# Temperature.net
KiCad netlist of a schematic drawn in Altium Designer
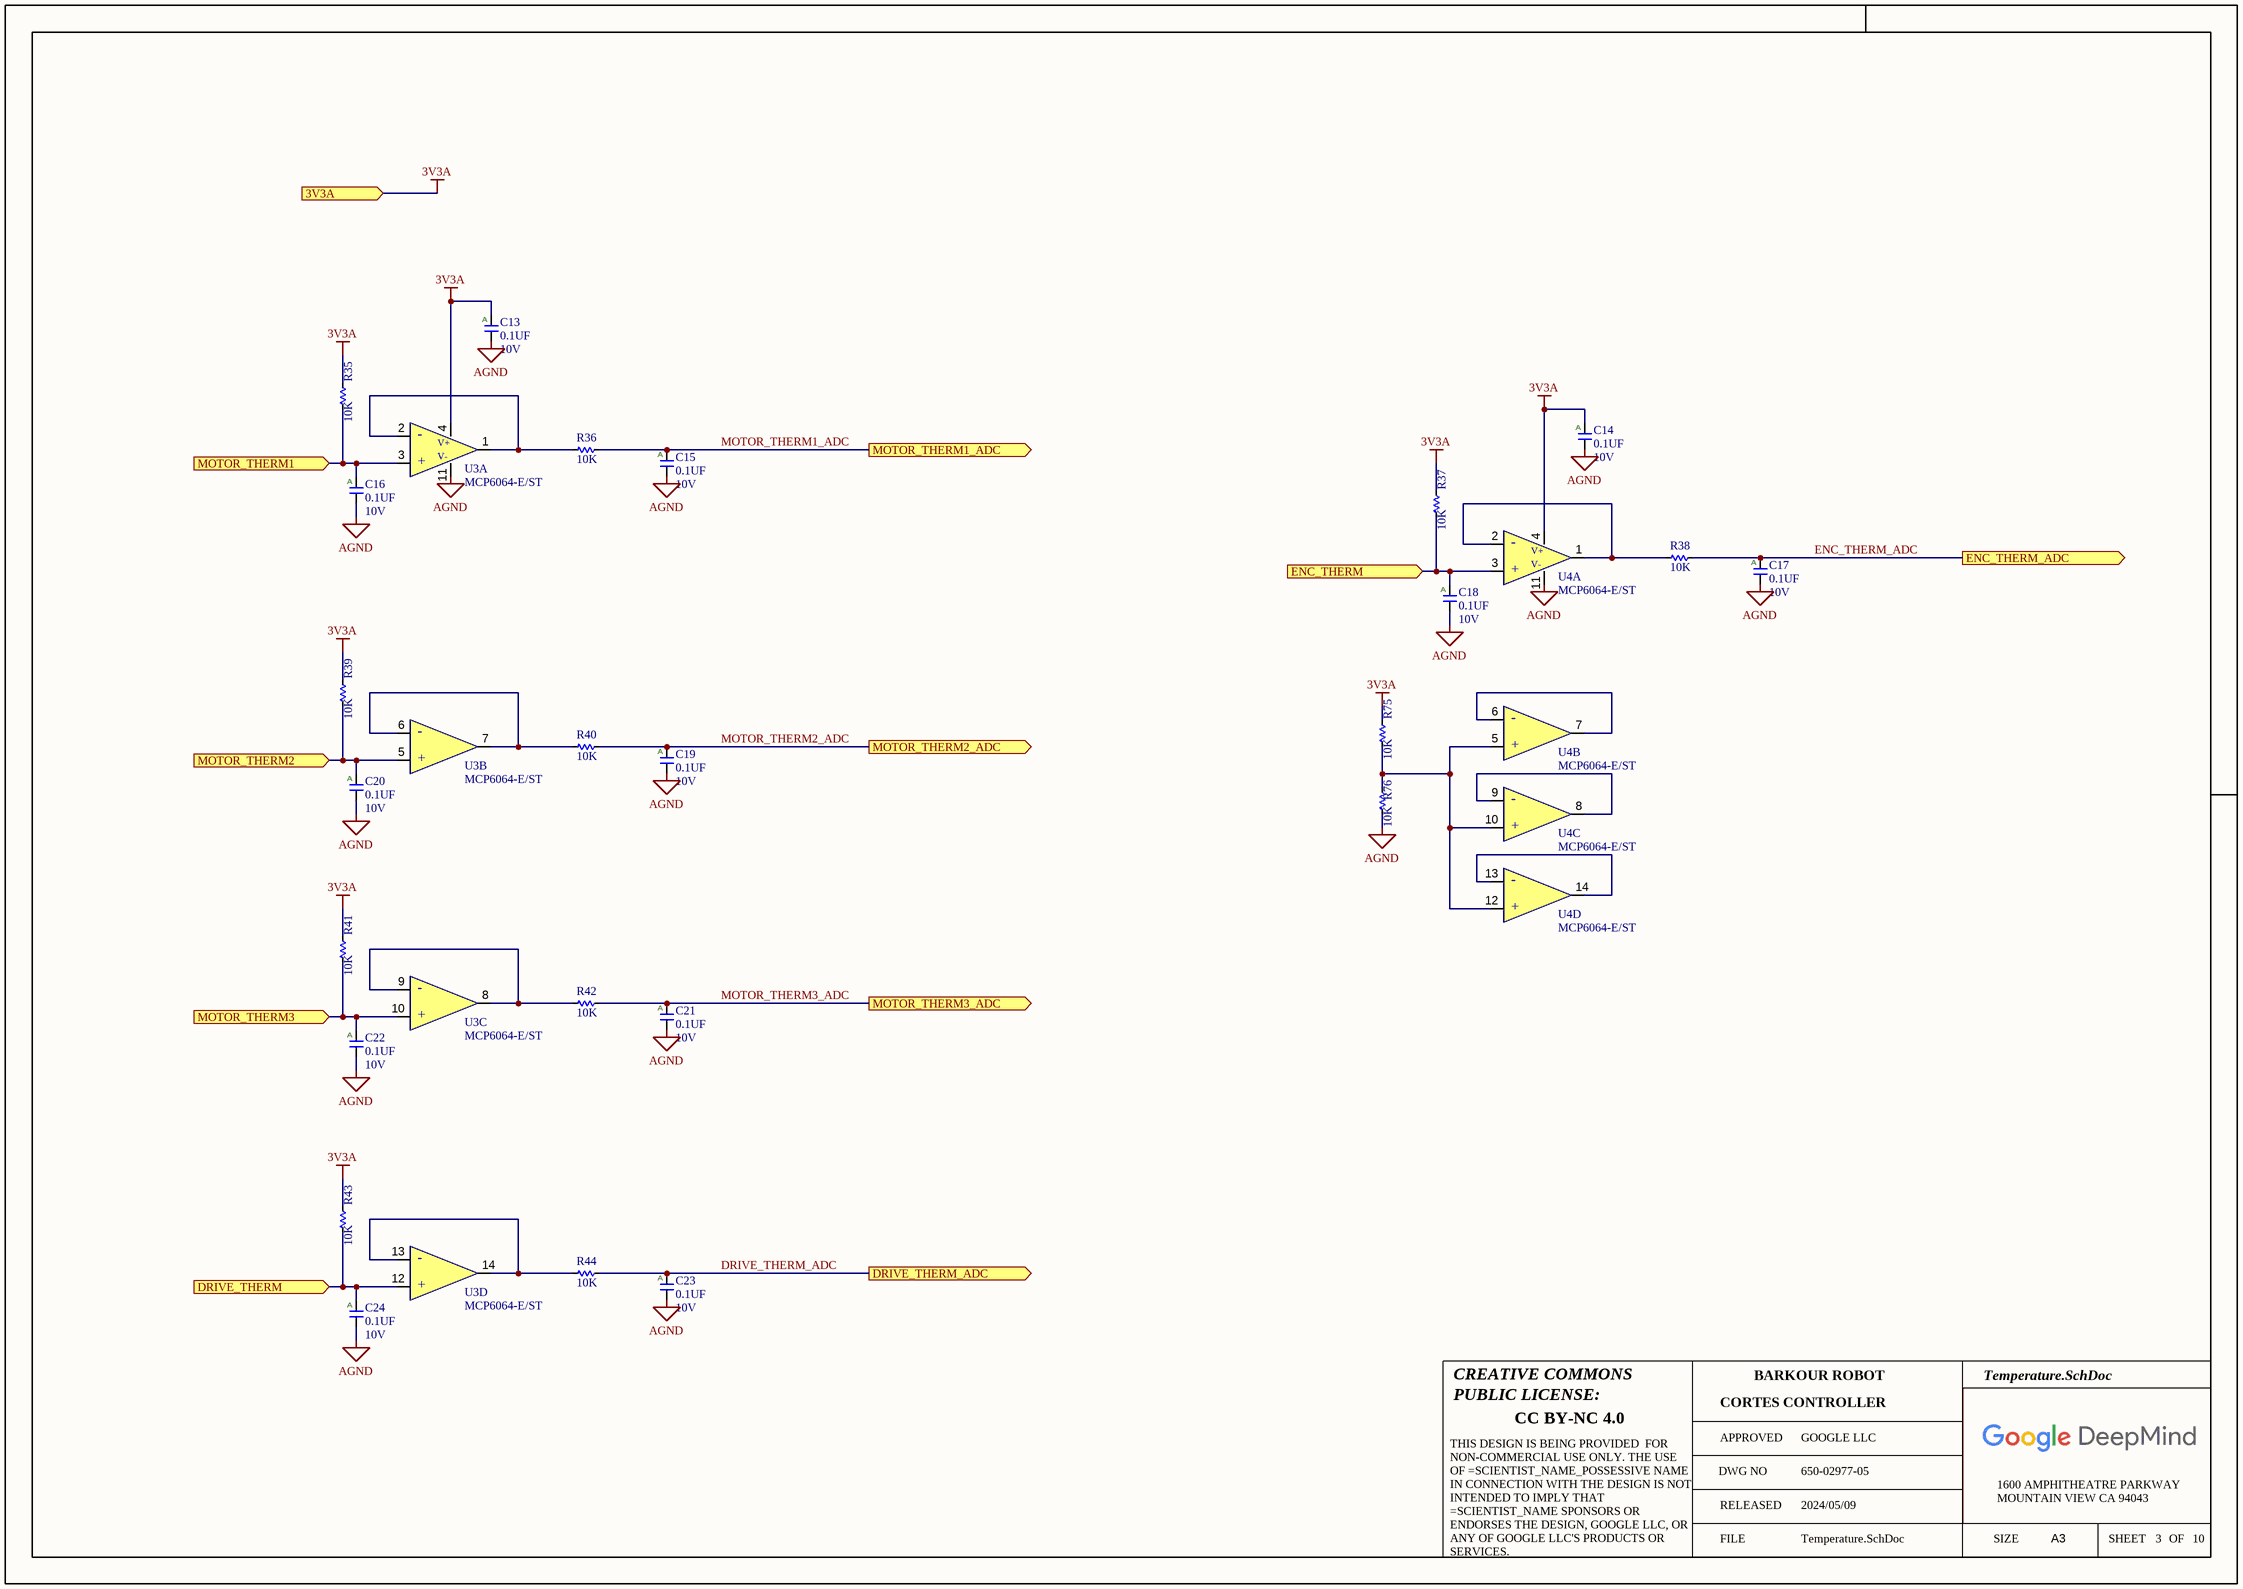
[diagram p0: Temperature.SchDoc]

(export (version "E")
  (design (tool "Eeschema 10.0.6"))
  (components
    (comp (ref "C13")
      (value "0.1UF")
      (footprint "C0201Y")
      (description "CAP, CER, X6S, 0.1uF, 10V, 10%, 0201, AUTOGRADE")
      (fields (field (name "MFG") "MURATA") (field (name "VOLTAGE") "10V") (field (name "TOLERANCE") "10%"))
      (libsource (lib "AltiumReleaseLibDB") (part "__Template_Cap_Auto"))
    )
    (comp (ref "C14")
      (value "0.1UF")
      (footprint "C0201Y")
      (description "CAP, CER, X6S, 0.1uF, 10V, 10%, 0201, AUTOGRADE")
      (fields (field (name "MFG") "MURATA") (field (name "VOLTAGE") "10V") (field (name "TOLERANCE") "10%"))
      (libsource (lib "AltiumReleaseLibDB") (part "__Template_Cap_Auto"))
    )
    (comp (ref "C15")
      (value "0.1UF")
      (footprint "C0201Y")
      (description "CAP, CER, X6S, 0.1uF, 10V, 10%, 0201, AUTOGRADE")
      (fields (field (name "MFG") "MURATA") (field (name "VOLTAGE") "10V") (field (name "TOLERANCE") "10%"))
      (libsource (lib "AltiumReleaseLibDB") (part "__Template_Cap_Auto"))
    )
    (comp (ref "C16")
      (value "0.1UF")
      (footprint "C0201Y")
      (description "CAP, CER, X6S, 0.1uF, 10V, 10%, 0201, AUTOGRADE")
      (fields (field (name "MFG") "MURATA") (field (name "VOLTAGE") "10V") (field (name "TOLERANCE") "10%"))
      (libsource (lib "AltiumReleaseLibDB") (part "__Template_Cap_Auto"))
    )
    (comp (ref "C17")
      (value "0.1UF")
      (footprint "C0201Y")
      (description "CAP, CER, X6S, 0.1uF, 10V, 10%, 0201, AUTOGRADE")
      (fields (field (name "MFG") "MURATA") (field (name "VOLTAGE") "10V") (field (name "TOLERANCE") "10%"))
      (libsource (lib "AltiumReleaseLibDB") (part "__Template_Cap_Auto"))
    )
    (comp (ref "C18")
      (value "0.1UF")
      (footprint "C0201Y")
      (description "CAP, CER, X6S, 0.1uF, 10V, 10%, 0201, AUTOGRADE")
      (fields (field (name "MFG") "MURATA") (field (name "VOLTAGE") "10V") (field (name "TOLERANCE") "10%"))
      (libsource (lib "AltiumReleaseLibDB") (part "__Template_Cap_Auto"))
    )
    (comp (ref "C19")
      (value "0.1UF")
      (footprint "C0201Y")
      (description "CAP, CER, X6S, 0.1uF, 10V, 10%, 0201, AUTOGRADE")
      (fields (field (name "MFG") "MURATA") (field (name "VOLTAGE") "10V") (field (name "TOLERANCE") "10%"))
      (libsource (lib "AltiumReleaseLibDB") (part "__Template_Cap_Auto"))
    )
    (comp (ref "C20")
      (value "0.1UF")
      (footprint "C0201Y")
      (description "CAP, CER, X6S, 0.1uF, 10V, 10%, 0201, AUTOGRADE")
      (fields (field (name "MFG") "MURATA") (field (name "VOLTAGE") "10V") (field (name "TOLERANCE") "10%"))
      (libsource (lib "AltiumReleaseLibDB") (part "__Template_Cap_Auto"))
    )
    (comp (ref "C21")
      (value "0.1UF")
      (footprint "C0201Y")
      (description "CAP, CER, X6S, 0.1uF, 10V, 10%, 0201, AUTOGRADE")
      (fields (field (name "MFG") "MURATA") (field (name "VOLTAGE") "10V") (field (name "TOLERANCE") "10%"))
      (libsource (lib "AltiumReleaseLibDB") (part "__Template_Cap_Auto"))
    )
    (comp (ref "C22")
      (value "0.1UF")
      (footprint "C0201Y")
      (description "CAP, CER, X6S, 0.1uF, 10V, 10%, 0201, AUTOGRADE")
      (fields (field (name "MFG") "MURATA") (field (name "VOLTAGE") "10V") (field (name "TOLERANCE") "10%"))
      (libsource (lib "AltiumReleaseLibDB") (part "__Template_Cap_Auto"))
    )
    (comp (ref "C23")
      (value "0.1UF")
      (footprint "C0201Y")
      (description "CAP, CER, X6S, 0.1uF, 10V, 10%, 0201, AUTOGRADE")
      (fields (field (name "MFG") "MURATA") (field (name "VOLTAGE") "10V") (field (name "TOLERANCE") "10%"))
      (libsource (lib "AltiumReleaseLibDB") (part "__Template_Cap_Auto"))
    )
    (comp (ref "C24")
      (value "0.1UF")
      (footprint "C0201Y")
      (description "CAP, CER, X6S, 0.1uF, 10V, 10%, 0201, AUTOGRADE")
      (fields (field (name "MFG") "MURATA") (field (name "VOLTAGE") "10V") (field (name "TOLERANCE") "10%"))
      (libsource (lib "AltiumReleaseLibDB") (part "__Template_Cap_Auto"))
    )
    (comp (ref "R35")
      (value "10K")
      (footprint "R0201_H0.26MM")
      (description "RES, 10K, 1%, 1/20W, 0201, AUTOGRADE")
      (fields (field (name "MFG") "PANASONIC") (field (name "POWER") "1/20W"))
      (libsource (lib "AltiumReleaseLibDB") (part "__Template_Resistor"))
    )
    (comp (ref "R36")
      (value "10K")
      (footprint "R0201_H0.26MM")
      (description "RES, 10K, 1%, 1/20W, 0201, AUTOGRADE")
      (fields (field (name "MFG") "PANASONIC") (field (name "POWER") "1/20W"))
      (libsource (lib "AltiumReleaseLibDB") (part "__Template_Resistor"))
    )
    (comp (ref "R37")
      (value "10K")
      (footprint "R0201_H0.26MM")
      (description "RES, 10K, 1%, 1/20W, 0201, AUTOGRADE")
      (fields (field (name "MFG") "PANASONIC") (field (name "POWER") "1/20W"))
      (libsource (lib "AltiumReleaseLibDB") (part "__Template_Resistor"))
    )
    (comp (ref "R38")
      (value "10K")
      (footprint "R0201_H0.26MM")
      (description "RES, 10K, 1%, 1/20W, 0201, AUTOGRADE")
      (fields (field (name "MFG") "PANASONIC") (field (name "POWER") "1/20W"))
      (libsource (lib "AltiumReleaseLibDB") (part "__Template_Resistor"))
    )
    (comp (ref "R39")
      (value "10K")
      (footprint "R0201_H0.26MM")
      (description "RES, 10K, 1%, 1/20W, 0201, AUTOGRADE")
      (fields (field (name "MFG") "PANASONIC") (field (name "POWER") "1/20W"))
      (libsource (lib "AltiumReleaseLibDB") (part "__Template_Resistor"))
    )
    (comp (ref "R40")
      (value "10K")
      (footprint "R0201_H0.26MM")
      (description "RES, 10K, 1%, 1/20W, 0201, AUTOGRADE")
      (fields (field (name "MFG") "PANASONIC") (field (name "POWER") "1/20W"))
      (libsource (lib "AltiumReleaseLibDB") (part "__Template_Resistor"))
    )
    (comp (ref "R41")
      (value "10K")
      (footprint "R0201_H0.26MM")
      (description "RES, 10K, 1%, 1/20W, 0201, AUTOGRADE")
      (fields (field (name "MFG") "PANASONIC") (field (name "POWER") "1/20W"))
      (libsource (lib "AltiumReleaseLibDB") (part "__Template_Resistor"))
    )
    (comp (ref "R42")
      (value "10K")
      (footprint "R0201_H0.26MM")
      (description "RES, 10K, 1%, 1/20W, 0201, AUTOGRADE")
      (fields (field (name "MFG") "PANASONIC") (field (name "POWER") "1/20W"))
      (libsource (lib "AltiumReleaseLibDB") (part "__Template_Resistor"))
    )
    (comp (ref "R43")
      (value "10K")
      (footprint "R0201_H0.26MM")
      (description "RES, 10K, 1%, 1/20W, 0201, AUTOGRADE")
      (fields (field (name "MFG") "PANASONIC") (field (name "POWER") "1/20W"))
      (libsource (lib "AltiumReleaseLibDB") (part "__Template_Resistor"))
    )
    (comp (ref "R44")
      (value "10K")
      (footprint "R0201_H0.26MM")
      (description "RES, 10K, 1%, 1/20W, 0201, AUTOGRADE")
      (fields (field (name "MFG") "PANASONIC") (field (name "POWER") "1/20W"))
      (libsource (lib "AltiumReleaseLibDB") (part "__Template_Resistor"))
    )
    (comp (ref "R75")
      (value "10K")
      (footprint "R0201_H0.26MM")
      (description "RES, 10K, 1%, 1/20W, 0201, AUTOGRADE")
      (fields (field (name "MFG") "PANASONIC") (field (name "POWER") "1/20W"))
      (libsource (lib "AltiumReleaseLibDB") (part "__Template_Resistor"))
    )
    (comp (ref "R76")
      (value "10K")
      (footprint "R0201_H0.26MM")
      (description "RES, 10K, 1%, 1/20W, 0201, AUTOGRADE")
      (fields (field (name "MFG") "PANASONIC") (field (name "POWER") "1/20W"))
      (libsource (lib "AltiumReleaseLibDB") (part "__Template_Resistor"))
    )
    (comp (ref "U3")
      (value "MCP6064")
      (footprint "14TSSOP65")
      (description "Microchip MCP6064-E/ST; Quad Op Amp; 0.73MHz CMOS; Rail to Rail; 3V; 5V; 14-Pin TSSOP")
      (fields
        (field (name "MANUFACTURER") "Microchip")
        (field (name "MANUFACTURER PART NUMBER") "MCP6064-E/ST")
      )
      (libsource (lib "MiscSch1") (part "MICROCHIP_MCP6064"))
    )
    (comp (ref "U4")
      (value "MCP6064")
      (footprint "14TSSOP65")
      (description "Microchip MCP6064-E/ST; Quad Op Amp; 0.73MHz CMOS; Rail to Rail; 3V; 5V; 14-Pin TSSOP")
      (fields
        (field (name "MANUFACTURER") "Microchip")
        (field (name "MANUFACTURER PART NUMBER") "MCP6064-E/ST")
      )
      (libsource (lib "MiscSch1") (part "MICROCHIP_MCP6064"))
    )
  )
  (nets
    (net (code "1") (name "/DRIVE_THERM") (class "Default")
      (node (ref "C24") (pin "1") (pintype "passive"))
      (node (ref "R43") (pin "1") (pintype "passive"))
      (node (ref "U3") (pin "12") (pinfunction "12_12") (pintype "passive"))
    )
    (net (code "2") (name "/DRIVE_THERM_ADC") (class "Default")
      (node (ref "C23") (pin "1") (pintype "passive"))
      (node (ref "R44") (pin "2") (pintype "passive"))
    )
    (net (code "3") (name "/ENC_THERM") (class "Default")
      (node (ref "C18") (pin "1") (pintype "passive"))
      (node (ref "R37") (pin "1") (pintype "passive"))
      (node (ref "U4") (pin "3") (pinfunction "3_3") (pintype "passive"))
    )
    (net (code "4") (name "/ENC_THERM_ADC") (class "Default")
      (node (ref "C17") (pin "1") (pintype "passive"))
      (node (ref "R38") (pin "2") (pintype "passive"))
    )
    (net (code "5") (name "/MOTOR_THERM1") (class "Default")
      (node (ref "C16") (pin "1") (pintype "passive"))
      (node (ref "R35") (pin "1") (pintype "passive"))
      (node (ref "U3") (pin "3") (pinfunction "3_3") (pintype "passive"))
    )
    (net (code "6") (name "/MOTOR_THERM1_ADC") (class "Default")
      (node (ref "C15") (pin "1") (pintype "passive"))
      (node (ref "R36") (pin "2") (pintype "passive"))
    )
    (net (code "7") (name "/MOTOR_THERM2") (class "Default")
      (node (ref "C20") (pin "1") (pintype "passive"))
      (node (ref "R39") (pin "1") (pintype "passive"))
      (node (ref "U3") (pin "5") (pinfunction "5_5") (pintype "passive"))
    )
    (net (code "8") (name "/MOTOR_THERM2_ADC") (class "Default")
      (node (ref "C19") (pin "1") (pintype "passive"))
      (node (ref "R40") (pin "2") (pintype "passive"))
    )
    (net (code "9") (name "/MOTOR_THERM3") (class "Default")
      (node (ref "C22") (pin "1") (pintype "passive"))
      (node (ref "R41") (pin "1") (pintype "passive"))
      (node (ref "U3") (pin "10") (pinfunction "10_10") (pintype "passive"))
    )
    (net (code "10") (name "/MOTOR_THERM3_ADC") (class "Default")
      (node (ref "C21") (pin "1") (pintype "passive"))
      (node (ref "R42") (pin "2") (pintype "passive"))
    )
    (net (code "11") (name "3V3A") (class "Default")
      (node (ref "C13") (pin "1") (pintype "passive"))
      (node (ref "C14") (pin "1") (pintype "passive"))
      (node (ref "R35") (pin "2") (pintype "passive"))
      (node (ref "R37") (pin "2") (pintype "passive"))
      (node (ref "R39") (pin "2") (pintype "passive"))
      (node (ref "R41") (pin "2") (pintype "passive"))
      (node (ref "R43") (pin "2") (pintype "passive"))
      (node (ref "R75") (pin "2") (pintype "passive"))
      (node (ref "U3") (pin "4") (pinfunction "4_4") (pintype "passive"))
      (node (ref "U4") (pin "4") (pinfunction "4_4") (pintype "passive"))
    )
    (net (code "12") (name "AGND") (class "Default")
      (node (ref "C13") (pin "2") (pintype "passive"))
      (node (ref "C14") (pin "2") (pintype "passive"))
      (node (ref "C15") (pin "2") (pintype "passive"))
      (node (ref "C16") (pin "2") (pintype "passive"))
      (node (ref "C17") (pin "2") (pintype "passive"))
      (node (ref "C18") (pin "2") (pintype "passive"))
      (node (ref "C19") (pin "2") (pintype "passive"))
      (node (ref "C20") (pin "2") (pintype "passive"))
      (node (ref "C21") (pin "2") (pintype "passive"))
      (node (ref "C22") (pin "2") (pintype "passive"))
      (node (ref "C23") (pin "2") (pintype "passive"))
      (node (ref "C24") (pin "2") (pintype "passive"))
      (node (ref "R76") (pin "1") (pintype "passive"))
      (node (ref "U3") (pin "11") (pinfunction "11_11") (pintype "passive"))
      (node (ref "U4") (pin "11") (pinfunction "11_11") (pintype "passive"))
    )
    (net (code "13") (name "Net-(R36-Pad1)") (class "Default")
      (node (ref "R36") (pin "1") (pintype "passive"))
      (node (ref "U3") (pin "1") (pinfunction "1_1") (pintype "passive"))
      (node (ref "U3") (pin "2") (pinfunction "2_2") (pintype "passive"))
    )
    (net (code "14") (name "Net-(R38-Pad1)") (class "Default")
      (node (ref "R38") (pin "1") (pintype "passive"))
      (node (ref "U4") (pin "1") (pinfunction "1_1") (pintype "passive"))
      (node (ref "U4") (pin "2") (pinfunction "2_2") (pintype "passive"))
    )
    (net (code "15") (name "Net-(R40-Pad1)") (class "Default")
      (node (ref "R40") (pin "1") (pintype "passive"))
      (node (ref "U3") (pin "6") (pinfunction "6_6") (pintype "passive"))
      (node (ref "U3") (pin "7") (pinfunction "7_7") (pintype "passive"))
    )
    (net (code "16") (name "Net-(R42-Pad1)") (class "Default")
      (node (ref "R42") (pin "1") (pintype "passive"))
      (node (ref "U3") (pin "8") (pinfunction "8_8") (pintype "passive"))
      (node (ref "U3") (pin "9") (pinfunction "9_9") (pintype "passive"))
    )
    (net (code "17") (name "Net-(R44-Pad1)") (class "Default")
      (node (ref "R44") (pin "1") (pintype "passive"))
      (node (ref "U3") (pin "13") (pinfunction "13_13") (pintype "passive"))
      (node (ref "U3") (pin "14") (pinfunction "14_14") (pintype "passive"))
    )
    (net (code "18") (name "Net-(R75-Pad1)") (class "Default")
      (node (ref "R75") (pin "1") (pintype "passive"))
      (node (ref "R76") (pin "2") (pintype "passive"))
      (node (ref "U4") (pin "10") (pinfunction "10_10") (pintype "passive"))
      (node (ref "U4") (pin "12") (pinfunction "12_12") (pintype "passive"))
      (node (ref "U4") (pin "5") (pinfunction "5_5") (pintype "passive"))
    )
    (net (code "19") (name "Net-(U4-Pad6)") (class "Default")
      (node (ref "U4") (pin "6") (pinfunction "6_6") (pintype "passive"))
      (node (ref "U4") (pin "7") (pinfunction "7_7") (pintype "passive"))
    )
    (net (code "20") (name "Net-(U4-Pad8)") (class "Default")
      (node (ref "U4") (pin "8") (pinfunction "8_8") (pintype "passive"))
      (node (ref "U4") (pin "9") (pinfunction "9_9") (pintype "passive"))
    )
    (net (code "21") (name "Net-(U4-Pad13)") (class "Default")
      (node (ref "U4") (pin "13") (pinfunction "13_13") (pintype "passive"))
      (node (ref "U4") (pin "14") (pinfunction "14_14") (pintype "passive"))
    )
  )
)
